# 4_cyber60-alps_power.net
KiCad netlist of a schematic drawn in Altium Designer
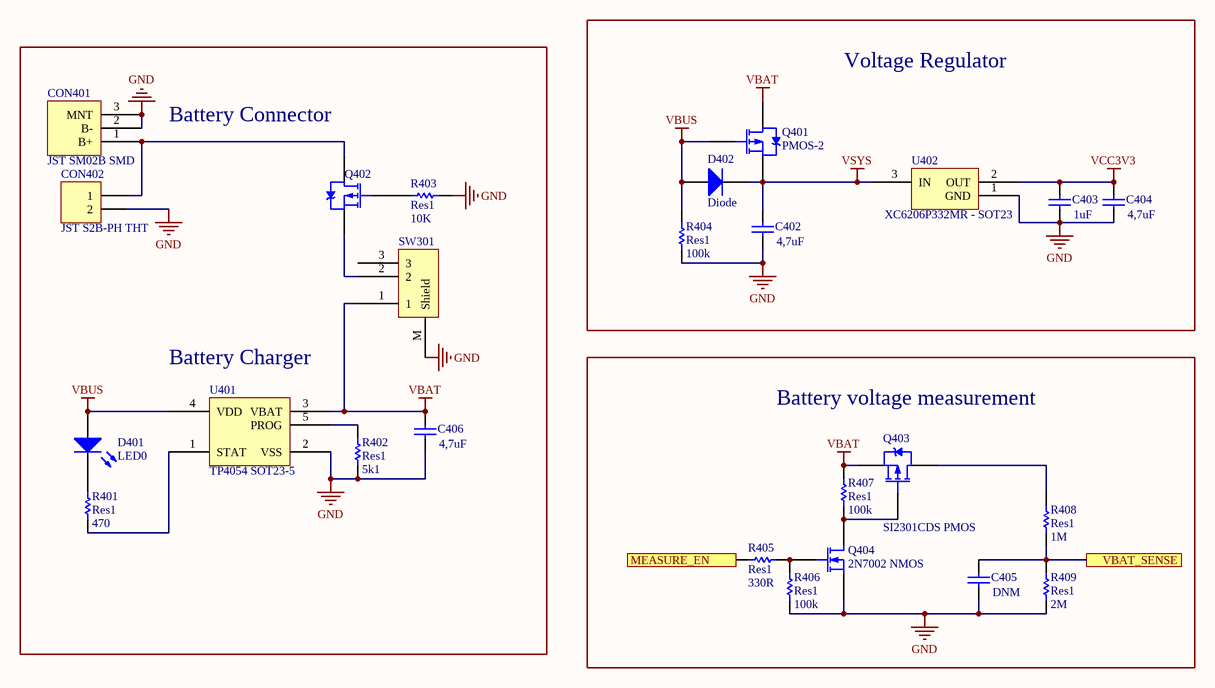
[diagram p0: 4_cyber60-alps_power.SchDoc]

(export (version "E")
  (design (tool "Eeschema 10.0.6"))
  (components
    (comp (ref "C402")
      (value "4,7uF")
      (footprint "C0603[1608]")
      (description "Capacitor")
      (fields (field (name "LCSC PART #") "C19666") (field (name "MRF.PART") "CL10A475KO8NNNC"))
      (libsource (lib "Miscellaneous Devices") (part "Cap"))
    )
    (comp (ref "C403")
      (value "1uF")
      (footprint "C0603[1608]")
      (description "Capacitor")
      (fields (field (name "MFG") "KEMET") (field (name "LCSC PART #") "C15849"))
      (libsource (lib "Miscellaneous Devices") (part "Cap"))
    )
    (comp (ref "C404")
      (value "4,7uF")
      (footprint "C0603[1608]")
      (description "Capacitor")
      (fields (field (name "LCSC PART #") "C19666") (field (name "MRF.PART") "CL10A475KO8NNNC"))
      (libsource (lib "Miscellaneous Devices") (part "Cap"))
    )
    (comp (ref "C405")
      (value "DNM")
      (footprint "C0603[1608]")
      (description "Capacitor")
      (libsource (lib "Miscellaneous Devices") (part "Cap"))
    )
    (comp (ref "C406")
      (value "4,7uF")
      (footprint "C0603[1608]")
      (description "Capacitor")
      (fields (field (name "LCSC PART #") "C19666") (field (name "MRF.PART") "CL10A475KO8NNNC"))
      (libsource (lib "Miscellaneous Devices") (part "Cap"))
    )
    (comp (ref "CON401")
      (value "JST SM02B SMD")
      (footprint "JST SM02B-SRSS-TB")
      (fields (field (name "LCSC PART #") "C160402") (field (name "MRF.PART") "SM02B-SRSS-TB(LF)(SN)"))
      (libsource (lib "Keebs") (part "JST S2B-PH-SM4-TB"))
    )
    (comp (ref "CON402")
      (value "JST S2B-PH THT")
      (footprint "Keebs:JST S2B-PH-K(LF)(SN)")
      (description "Header, 2-Pin")
      (fields (field (name "LCSC PART #") "C265016") (field (name "MRF.PART") "S2B-PH-K(LF)(SN)"))
      (libsource (lib "Miscellaneous Connectors") (part "Header 2"))
    )
    (comp (ref "D401")
      (value "LED0")
      (footprint "LED0603[1608]")
      (description "Typical INFRARED GaAs LED")
      (fields (field (name "LCSC PART #") "C72038") (field (name "MRF.PART") "19-213/Y2C-CQ2R2L/3T(CY)"))
      (libsource (lib "Miscellaneous Devices") (part "LED0"))
    )
    (comp (ref "D402")
      (value "Diode")
      (footprint "SOD-123")
      (description "Default Diode")
      (fields (field (name "LCSC PART #") "C8598") (field (name "MRF.PART") "B5819W"))
      (libsource (lib "Miscellaneous Devices") (part "Diode"))
    )
    (comp (ref "Q401")
      (value "PMOS-2")
      (footprint "SOT-23-3")
      (description "P-Channel Power MOSFET")
      (fields (field (name "MRF.PART") "SI2301CDS-T1-GE3") (field (name "LCSC PART #") "C10487"))
      (libsource (lib "Miscellaneous Devices") (part "PMOS-2"))
    )
    (comp (ref "Q402")
      (value "PMOS-2")
      (footprint "SOT-23-3")
      (description "P-Channel Power MOSFET")
      (fields (field (name "LCSC PART #") "C10487") (field (name "MRF.PART") "SI2301CDS-T1-GE3"))
      (libsource (lib "Miscellaneous Devices") (part "PMOS-2"))
    )
    (comp (ref "Q403")
      (value "SI2301CDS PMOS")
      (footprint "SOT-23-3")
      (description "P-Channel Power MOSFET")
      (fields (field (name "MRF.PART") "SI2301CDS-T1-GE3") (field (name "LCSC PART #") "C10487"))
      (libsource (lib "Miscellaneous Devices") (part "PMOS-2"))
    )
    (comp (ref "Q404")
      (value "2N7002 NMOS")
      (footprint "SOT-23-3")
      (description "N-Channel MOSFET")
      (fields (field (name "LCSC PART #") "C8545") (field (name "MRF.PART") "2N7002"))
      (libsource (lib "Miscellaneous Devices") (part "MOSFET-N"))
    )
    (comp (ref "R401")
      (value "Res1")
      (footprint "R0603[1608]")
      (description "Resistor")
      (fields
        (field (name "ALTIUM_VALUE") "470")
        (field (name "MFG") "Panasonic Electronic Components")
        (field (name "LCSC PART #") "C23179")
      )
      (libsource (lib "Miscellaneous Devices") (part "Res1"))
    )
    (comp (ref "R402")
      (value "Res1")
      (footprint "R0603[1608]")
      (description "Resistor")
      (fields
        (field (name "ALTIUM_VALUE") "5k1")
        (field (name "MFG") "Panasonic Electronic Components")
        (field (name "LCSC PART #") "C23186")
      )
      (libsource (lib "Miscellaneous Devices") (part "Res1"))
    )
    (comp (ref "R403")
      (value "Res1")
      (footprint "R0603[1608]")
      (description "Resistor")
      (fields
        (field (name "ALTIUM_VALUE") "10K")
        (field (name "MFG") "Panasonic Electronic Components")
        (field (name "LCSC PART #") "C25804")
      )
      (libsource (lib "Miscellaneous Devices") (part "Res1"))
    )
    (comp (ref "R404")
      (value "Res1")
      (footprint "R0603[1608]")
      (description "Resistor")
      (fields
        (field (name "ALTIUM_VALUE") "100k")
        (field (name "MRF.PART") "0603WAF1003T5E")
        (field (name "LCSC PART #") "C25803")
      )
      (libsource (lib "Miscellaneous Devices") (part "Res1"))
    )
    (comp (ref "R405")
      (value "Res1")
      (footprint "R0603[1608]")
      (description "Resistor")
      (fields
        (field (name "ALTIUM_VALUE") "330R")
        (field (name "LCSC PART #") "C23138")
        (field (name "MRF.PART") "0603WAF3300T5E")
      )
      (libsource (lib "Miscellaneous Devices") (part "Res1"))
    )
    (comp (ref "R406")
      (value "Res1")
      (footprint "R0603[1608]")
      (description "Resistor")
      (fields
        (field (name "ALTIUM_VALUE") "100k")
        (field (name "MRF.PART") "0603WAF1003T5E")
        (field (name "LCSC PART #") "C25803")
      )
      (libsource (lib "Miscellaneous Devices") (part "Res1"))
    )
    (comp (ref "R407")
      (value "Res1")
      (footprint "R0603[1608]")
      (description "Resistor")
      (fields
        (field (name "ALTIUM_VALUE") "100k")
        (field (name "MRF.PART") "0603WAF1003T5E")
        (field (name "LCSC PART #") "C25803")
      )
      (libsource (lib "Miscellaneous Devices") (part "Res1"))
    )
    (comp (ref "R408")
      (value "Res1")
      (footprint "R0603[1608]")
      (description "Resistor")
      (fields
        (field (name "ALTIUM_VALUE") "1M")
        (field (name "MRF.PART") "0603WAF1004T5E")
        (field (name "LCSC PART #") "C22935")
      )
      (libsource (lib "Miscellaneous Devices") (part "Res1"))
    )
    (comp (ref "R409")
      (value "Res1")
      (footprint "R0603[1608]")
      (description "Resistor")
      (fields
        (field (name "ALTIUM_VALUE") "2M")
        (field (name "MRF.PART") "0603WAF2004T5E")
        (field (name "LCSC PART #") "C22976")
      )
      (libsource (lib "Miscellaneous Devices") (part "Res1"))
    )
    (comp (ref "SW301")
      (value "Korean Hroparts Elec K3-1296S-E2")
      (footprint "Korean Hroparts Elec K3-1296S-E2")
      (fields (field (name "LCSC PART #") "C136659"))
      (libsource (lib "Keebs") (part "Korean Hroparts Elec K3-1296S-E2"))
    )
    (comp (ref "U401")
      (value "TP4054 SOT23-5")
      (footprint "SOT-23-5")
      (fields (field (name "LCSC PART #") "C32574") (field (name "MRF.PART") "TP4054"))
      (libsource (lib "Keebs") (part "MCP73831"))
    )
    (comp (ref "U402")
      (value "XC6206P332MR - SOT23")
      (footprint "SOT-23-3")
      (fields
        (field (name "LCSC PART #") "C5446")
        (field (name "MRF.PART") "XC6206P332MR")
        (field (name "MFG") "Texas Instruments")
      )
      (libsource (lib "Keebs") (part "SOT23 LDO"))
    )
  )
  (nets
    (net (code "1") (name "/MEASURE_EN") (class "Default")
      (node (ref "R405") (pin "1") (pinfunction "1_1") (pintype "passive"))
    )
    (net (code "2") (name "/VBAT_SENSE") (class "Default")
      (node (ref "C405") (pin "2") (pinfunction "2_2") (pintype "passive"))
      (node (ref "R408") (pin "2") (pinfunction "2_2") (pintype "passive"))
      (node (ref "R409") (pin "1") (pinfunction "1_1") (pintype "passive"))
    )
    (net (code "3") (name "GND") (class "Default")
      (node (ref "C402") (pin "1") (pinfunction "1_1") (pintype "passive"))
      (node (ref "C403") (pin "1") (pinfunction "1_1") (pintype "passive"))
      (node (ref "C404") (pin "1") (pinfunction "1_1") (pintype "passive"))
      (node (ref "C405") (pin "1") (pinfunction "1_1") (pintype "passive"))
      (node (ref "C406") (pin "1") (pinfunction "1_1") (pintype "passive"))
      (node (ref "CON401") (pin "2") (pinfunction "B-_2") (pintype "passive"))
      (node (ref "CON401") (pin "3") (pinfunction "MNT_3") (pintype "passive"))
      (node (ref "CON402") (pin "2") (pinfunction "2_2") (pintype "passive"))
      (node (ref "Q404") (pin "2") (pinfunction "S_2") (pintype "passive"))
      (node (ref "R402") (pin "2") (pinfunction "2_2") (pintype "passive"))
      (node (ref "R403") (pin "2") (pinfunction "2_2") (pintype "passive"))
      (node (ref "R404") (pin "2") (pinfunction "2_2") (pintype "passive"))
      (node (ref "R406") (pin "2") (pinfunction "2_2") (pintype "passive"))
      (node (ref "R409") (pin "2") (pinfunction "2_2") (pintype "passive"))
      (node (ref "SW301") (pin "M") (pinfunction "Shield_M") (pintype "passive"))
      (node (ref "U401") (pin "2") (pinfunction "VSS_2") (pintype "passive"))
      (node (ref "U402") (pin "1") (pinfunction "GND_1") (pintype "passive"))
    )
    (net (code "4") (name "Net-(CON401-B+)") (class "Default")
      (node (ref "CON401") (pin "1") (pinfunction "B+_1") (pintype "passive"))
      (node (ref "CON402") (pin "1") (pinfunction "1_1") (pintype "passive"))
      (node (ref "Q402") (pin "3") (pinfunction "D_3") (pintype "passive"))
    )
    (net (code "5") (name "Net-(D401-K)") (class "Default")
      (node (ref "D401") (pin "2") (pinfunction "K_2") (pintype "passive"))
      (node (ref "R401") (pin "2") (pinfunction "2_2") (pintype "passive"))
    )
    (net (code "6") (name "Net-(Q402-G)") (class "Default")
      (node (ref "Q402") (pin "1") (pinfunction "G_1") (pintype "passive"))
      (node (ref "R403") (pin "1") (pinfunction "1_1") (pintype "passive"))
    )
    (net (code "7") (name "Net-(Q402-S)") (class "Default")
      (node (ref "Q402") (pin "2") (pinfunction "S_2") (pintype "passive"))
      (node (ref "SW301") (pin "2") (pinfunction "2_2") (pintype "passive"))
    )
    (net (code "8") (name "Net-(Q403-D)") (class "Default")
      (node (ref "Q403") (pin "3") (pinfunction "D_3") (pintype "passive"))
      (node (ref "R408") (pin "1") (pinfunction "1_1") (pintype "passive"))
    )
    (net (code "9") (name "Net-(Q403-G)") (class "Default")
      (node (ref "Q403") (pin "1") (pinfunction "G_1") (pintype "passive"))
      (node (ref "Q404") (pin "3") (pinfunction "D_3") (pintype "passive"))
      (node (ref "R407") (pin "2") (pinfunction "2_2") (pintype "passive"))
    )
    (net (code "10") (name "Net-(Q404-G)") (class "Default")
      (node (ref "Q404") (pin "1") (pinfunction "G_1") (pintype "passive"))
      (node (ref "R405") (pin "2") (pinfunction "2_2") (pintype "passive"))
      (node (ref "R406") (pin "1") (pinfunction "1_1") (pintype "passive"))
    )
    (net (code "11") (name "Net-(U401-PROG)") (class "Default")
      (node (ref "R402") (pin "1") (pinfunction "1_1") (pintype "passive"))
      (node (ref "U401") (pin "5") (pinfunction "PROG_5") (pintype "passive"))
    )
    (net (code "12") (name "Net-(U401-STAT)") (class "Default")
      (node (ref "R401") (pin "1") (pinfunction "1_1") (pintype "passive"))
      (node (ref "U401") (pin "1") (pinfunction "STAT_1") (pintype "passive"))
    )
    (net (code "13") (name "VBAT") (class "Default")
      (node (ref "C406") (pin "2") (pinfunction "2_2") (pintype "passive"))
      (node (ref "Q401") (pin "3") (pinfunction "D_3") (pintype "passive"))
      (node (ref "Q403") (pin "2") (pinfunction "S_2") (pintype "passive"))
      (node (ref "R407") (pin "1") (pinfunction "1_1") (pintype "passive"))
      (node (ref "SW301") (pin "1") (pinfunction "1_1") (pintype "passive"))
      (node (ref "U401") (pin "3") (pinfunction "VBAT_3") (pintype "passive"))
    )
    (net (code "14") (name "VBUS") (class "Default")
      (node (ref "D401") (pin "1") (pinfunction "A_1") (pintype "passive"))
      (node (ref "D402") (pin "1") (pinfunction "A_1") (pintype "passive"))
      (node (ref "Q401") (pin "1") (pinfunction "G_1") (pintype "passive"))
      (node (ref "R404") (pin "1") (pinfunction "1_1") (pintype "passive"))
      (node (ref "U401") (pin "4") (pinfunction "VDD_4") (pintype "passive"))
    )
    (net (code "15") (name "VCC3V3") (class "Default")
      (node (ref "C403") (pin "2") (pinfunction "2_2") (pintype "passive"))
      (node (ref "C404") (pin "2") (pinfunction "2_2") (pintype "passive"))
      (node (ref "U402") (pin "2") (pinfunction "OUT_2") (pintype "passive"))
    )
    (net (code "16") (name "VSYS") (class "Default")
      (node (ref "C402") (pin "2") (pinfunction "2_2") (pintype "passive"))
      (node (ref "D402") (pin "2") (pinfunction "K_2") (pintype "passive"))
      (node (ref "Q401") (pin "2") (pinfunction "S_2") (pintype "passive"))
      (node (ref "U402") (pin "3") (pinfunction "IN_3") (pintype "passive"))
    )
    (net (code "17") (name "unconnected-(SW301-Pad3)") (class "Default")
      (node (ref "SW301") (pin "3") (pinfunction "3_3") (pintype "passive"))
    )
  )
)
